# Driver.net
KiCad netlist of a schematic drawn in Altium Designer
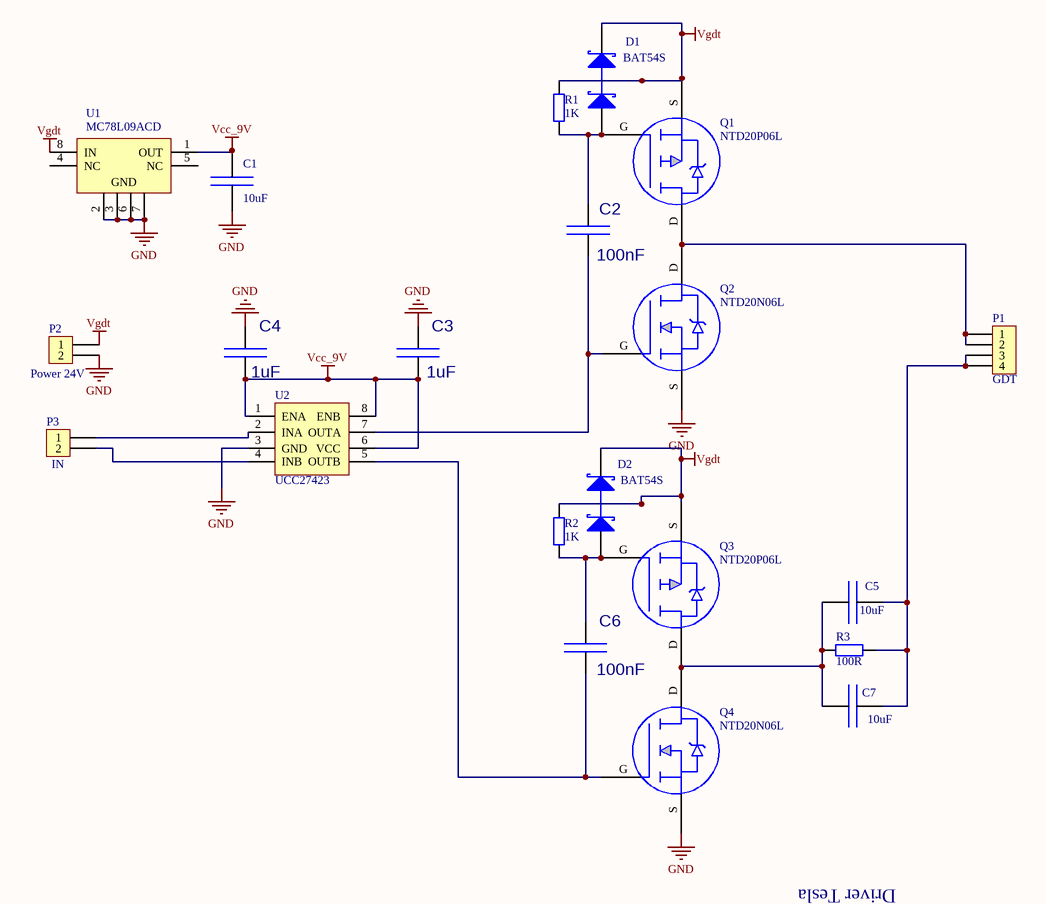
[diagram p0: Driver.SchDoc]

(export (version "E")
  (design (tool "Eeschema 10.0.6"))
  (components
    (comp (ref "C1")
      (value "SMD_1206")
      (footprint "SMD-1206")
      (fields (field (name "ALTIUM_UNNAMED_1") "10uF"))
      (libsource (lib "NEW") (part "Capasitor SMD_1206"))
    )
    (comp (ref "C2")
      (value "100nF")
      (footprint "C0805")
      (description "KONDENS_SMD")
      (libsource (lib "NEW") (part "KONDENS_SMD"))
    )
    (comp (ref "C3")
      (value "1uF")
      (footprint "C0805")
      (description "KONDENS_SMD")
      (libsource (lib "NEW") (part "KONDENS_SMD"))
    )
    (comp (ref "C4")
      (value "1uF")
      (footprint "C0805")
      (description "KONDENS_SMD")
      (libsource (lib "NEW") (part "KONDENS_SMD"))
    )
    (comp (ref "C5")
      (value "SMD_1206")
      (footprint "SMD-1206")
      (fields (field (name "ALTIUM_UNNAMED_1") "10uF"))
      (libsource (lib "NEW") (part "Capasitor SMD_1206"))
    )
    (comp (ref "C6")
      (value "100nF")
      (footprint "C0805")
      (description "KONDENS_SMD")
      (libsource (lib "NEW") (part "KONDENS_SMD"))
    )
    (comp (ref "C7")
      (value "SMD_1206")
      (footprint "SMD-1206")
      (fields (field (name "ALTIUM_UNNAMED_1") "10uF"))
      (libsource (lib "NEW") (part "Capasitor SMD_1206"))
    )
    (comp (ref "D1")
      (value "BAT54S")
      (footprint "SOT23_N")
      (description "Schottky Barrier Double Diode")
      (fields (field (name "PUBLISHER") "Altium Limited"))
      (libsource (lib "Philips Discrete Diode - Schottky") (part "BAT54S"))
    )
    (comp (ref "D2")
      (value "BAT54S")
      (footprint "SOT23_N")
      (description "Schottky Barrier Double Diode")
      (fields (field (name "PUBLISHER") "Altium Limited"))
      (libsource (lib "Philips Discrete Diode - Schottky") (part "BAT54S"))
    )
    (comp (ref "P1")
      (value "WF-04MR")
      (footprint "WF-04MR")
      (fields (field (name "ALTIUM_UNNAMED_1") "GDT"))
      (libsource (lib "NEW") (part "WF-04MR"))
    )
    (comp (ref "P2")
      (value "WF-02MR")
      (footprint "WF-02MR")
      (fields (field (name "ALTIUM_UNNAMED_1") "Power 24V"))
      (libsource (lib "NEW") (part "WF-02MR"))
    )
    (comp (ref "P3")
      (value "WF-02MR")
      (footprint "WF-02MR")
      (fields (field (name "ALTIUM_UNNAMED_1") "IN"))
      (libsource (lib "NEW") (part "WF-02MR"))
    )
    (comp (ref "Q1") (value "NTD20P06L") (footprint "DPAK") (libsource (lib "NEW") (part "NTD20P06L")))
    (comp (ref "Q2") (value "NTD20N06L") (footprint "DPAK") (libsource (lib "NEW") (part "NTD20N06L")))
    (comp (ref "Q3") (value "NTD20P06L") (footprint "DPAK") (libsource (lib "NEW") (part "NTD20P06L")))
    (comp (ref "Q4") (value "NTD20N06L") (footprint "DPAK") (libsource (lib "NEW") (part "NTD20N06L")))
    (comp (ref "R1")
      (value "1K")
      (footprint "C0805")
      (description "Resistor")
      (fields (field (name "Comment") "RES"))
      (libsource (lib "NEW") (part "RES"))
    )
    (comp (ref "R2")
      (value "1K")
      (footprint "C0805")
      (description "Resistor")
      (fields (field (name "Comment") "RES"))
      (libsource (lib "NEW") (part "RES"))
    )
    (comp (ref "R3")
      (value "1206")
      (footprint "SMD-1206")
      (fields (field (name "ALTIUM_UNNAMED_1") "100R"))
      (libsource (lib "NEW") (part "Resistor SMD_1206"))
    )
    (comp (ref "U1")
      (value "MC78L09ACD")
      (footprint "751-05_N")
      (description "Three-Terminal Low Current Positive Voltage Regulator")
      (fields (field (name "PUBLISHER") "Altium Limited"))
      (libsource (lib "ON Semi Power Mgt Voltage Regulator") (part "MC78L09ACD"))
    )
    (comp (ref "U2") (value "UCC27423") (footprint "PDIP") (libsource (lib "NEW") (part "UCC27423")))
  )
  (nets
    (net (code "1") (name "GND") (class "Default")
      (node (ref "C1") (pin "2") (pintype "passive"))
      (node (ref "C3") (pin "1") (pinfunction "A_1") (pintype "passive"))
      (node (ref "C4") (pin "1") (pinfunction "A_1") (pintype "passive"))
      (node (ref "P2") (pin "2") (pinfunction "2_2") (pintype "passive"))
      (node (ref "Q2") (pin "S") (pinfunction "Source_S") (pintype "passive"))
      (node (ref "Q4") (pin "S") (pinfunction "Source_S") (pintype "passive"))
      (node (ref "U1") (pin "2") (pinfunction "GND_2") (pintype "power_in"))
      (node (ref "U1") (pin "3") (pinfunction "GND_3") (pintype "power_in"))
      (node (ref "U1") (pin "6") (pinfunction "GND_6") (pintype "power_in"))
      (node (ref "U1") (pin "7") (pinfunction "GND_7") (pintype "power_in"))
      (node (ref "U2") (pin "3") (pinfunction "GND_3") (pintype "passive"))
    )
    (net (code "2") (name "Net-(C2-A)") (class "Default")
      (node (ref "C2") (pin "1") (pinfunction "A_1") (pintype "passive"))
      (node (ref "D1") (pin "1") (pinfunction "A_1") (pintype "passive"))
      (node (ref "Q1") (pin "G") (pinfunction "Gate_G") (pintype "passive"))
      (node (ref "R1") (pin "1") (pinfunction "1_1") (pintype "passive"))
    )
    (net (code "3") (name "Net-(C2-B)") (class "Default")
      (node (ref "C2") (pin "2") (pinfunction "B_2") (pintype "passive"))
      (node (ref "Q2") (pin "G") (pinfunction "Gate_G") (pintype "passive"))
      (node (ref "U2") (pin "7") (pinfunction "OUTA_7") (pintype "passive"))
    )
    (net (code "4") (name "Net-(C5-Pad2)") (class "Default")
      (node (ref "C5") (pin "2") (pintype "passive"))
      (node (ref "C7") (pin "2") (pintype "passive"))
      (node (ref "P1") (pin "3") (pinfunction "3_3") (pintype "passive"))
      (node (ref "P1") (pin "4") (pinfunction "4_4") (pintype "passive"))
      (node (ref "R3") (pin "1") (pinfunction "1_1") (pintype "passive"))
    )
    (net (code "5") (name "Net-(C6-A)") (class "Default")
      (node (ref "C6") (pin "1") (pinfunction "A_1") (pintype "passive"))
      (node (ref "D2") (pin "1") (pinfunction "A_1") (pintype "passive"))
      (node (ref "Q3") (pin "G") (pinfunction "Gate_G") (pintype "passive"))
      (node (ref "R2") (pin "1") (pinfunction "1_1") (pintype "passive"))
    )
    (net (code "6") (name "Net-(C6-B)") (class "Default")
      (node (ref "C6") (pin "2") (pinfunction "B_2") (pintype "passive"))
      (node (ref "Q4") (pin "G") (pinfunction "Gate_G") (pintype "passive"))
      (node (ref "U2") (pin "5") (pinfunction "OUTB_5") (pintype "passive"))
    )
    (net (code "7") (name "Net-(Q1-Drain)") (class "Default")
      (node (ref "P1") (pin "1") (pinfunction "1_1") (pintype "passive"))
      (node (ref "P1") (pin "2") (pinfunction "2_2") (pintype "passive"))
      (node (ref "Q1") (pin "D") (pinfunction "Drain_D") (pintype "passive"))
      (node (ref "Q2") (pin "D") (pinfunction "Drain_D") (pintype "passive"))
    )
    (net (code "8") (name "Net-(Q3-Drain)") (class "Default")
      (node (ref "C5") (pin "1") (pintype "passive"))
      (node (ref "C7") (pin "1") (pintype "passive"))
      (node (ref "Q3") (pin "D") (pinfunction "Drain_D") (pintype "passive"))
      (node (ref "Q4") (pin "D") (pinfunction "Drain_D") (pintype "passive"))
      (node (ref "R3") (pin "2") (pinfunction "2_2") (pintype "passive"))
    )
    (net (code "9") (name "Net-(U2-INA)") (class "Default")
      (node (ref "P3") (pin "1") (pinfunction "1_1") (pintype "passive"))
      (node (ref "U2") (pin "2") (pinfunction "INA_2") (pintype "passive"))
    )
    (net (code "10") (name "Net-(U2-INB)") (class "Default")
      (node (ref "P3") (pin "2") (pinfunction "2_2") (pintype "passive"))
      (node (ref "U2") (pin "4") (pinfunction "INB_4") (pintype "passive"))
    )
    (net (code "11") (name "Vcc_9V") (class "Default")
      (node (ref "C1") (pin "1") (pintype "passive"))
      (node (ref "C3") (pin "2") (pinfunction "B_2") (pintype "passive"))
      (node (ref "C4") (pin "2") (pinfunction "B_2") (pintype "passive"))
      (node (ref "U1") (pin "1") (pinfunction "OUT_1") (pintype "power_in"))
      (node (ref "U2") (pin "1") (pinfunction "ENA_1") (pintype "passive"))
      (node (ref "U2") (pin "6") (pinfunction "VCC_6") (pintype "passive"))
      (node (ref "U2") (pin "8") (pinfunction "ENB_8") (pintype "passive"))
    )
    (net (code "12") (name "Vgdt") (class "Default")
      (node (ref "D1") (pin "2") (pinfunction "K_2") (pintype "passive"))
      (node (ref "D1") (pin "3") (pinfunction "C_3") (pintype "passive"))
      (node (ref "D2") (pin "2") (pinfunction "K_2") (pintype "passive"))
      (node (ref "D2") (pin "3") (pinfunction "C_3") (pintype "passive"))
      (node (ref "P2") (pin "1") (pinfunction "1_1") (pintype "passive"))
      (node (ref "Q1") (pin "S") (pinfunction "Source_S") (pintype "passive"))
      (node (ref "Q3") (pin "S") (pinfunction "Source_S") (pintype "passive"))
      (node (ref "R1") (pin "2") (pinfunction "2_2") (pintype "passive"))
      (node (ref "R2") (pin "2") (pinfunction "2_2") (pintype "passive"))
      (node (ref "U1") (pin "8") (pinfunction "IN_8") (pintype "power_in"))
    )
    (net (code "13") (name "unconnected-(U1-NC-Pad4)") (class "Default")
      (node (ref "U1") (pin "4") (pinfunction "NC_4") (pintype "passive"))
    )
    (net (code "14") (name "unconnected-(U1-NC-Pad5)") (class "Default")
      (node (ref "U1") (pin "5") (pinfunction "NC_5") (pintype "passive"))
    )
  )
)
